# DIO-BNC_Supply.net
KiCad netlist of a schematic drawn in Altium Designer
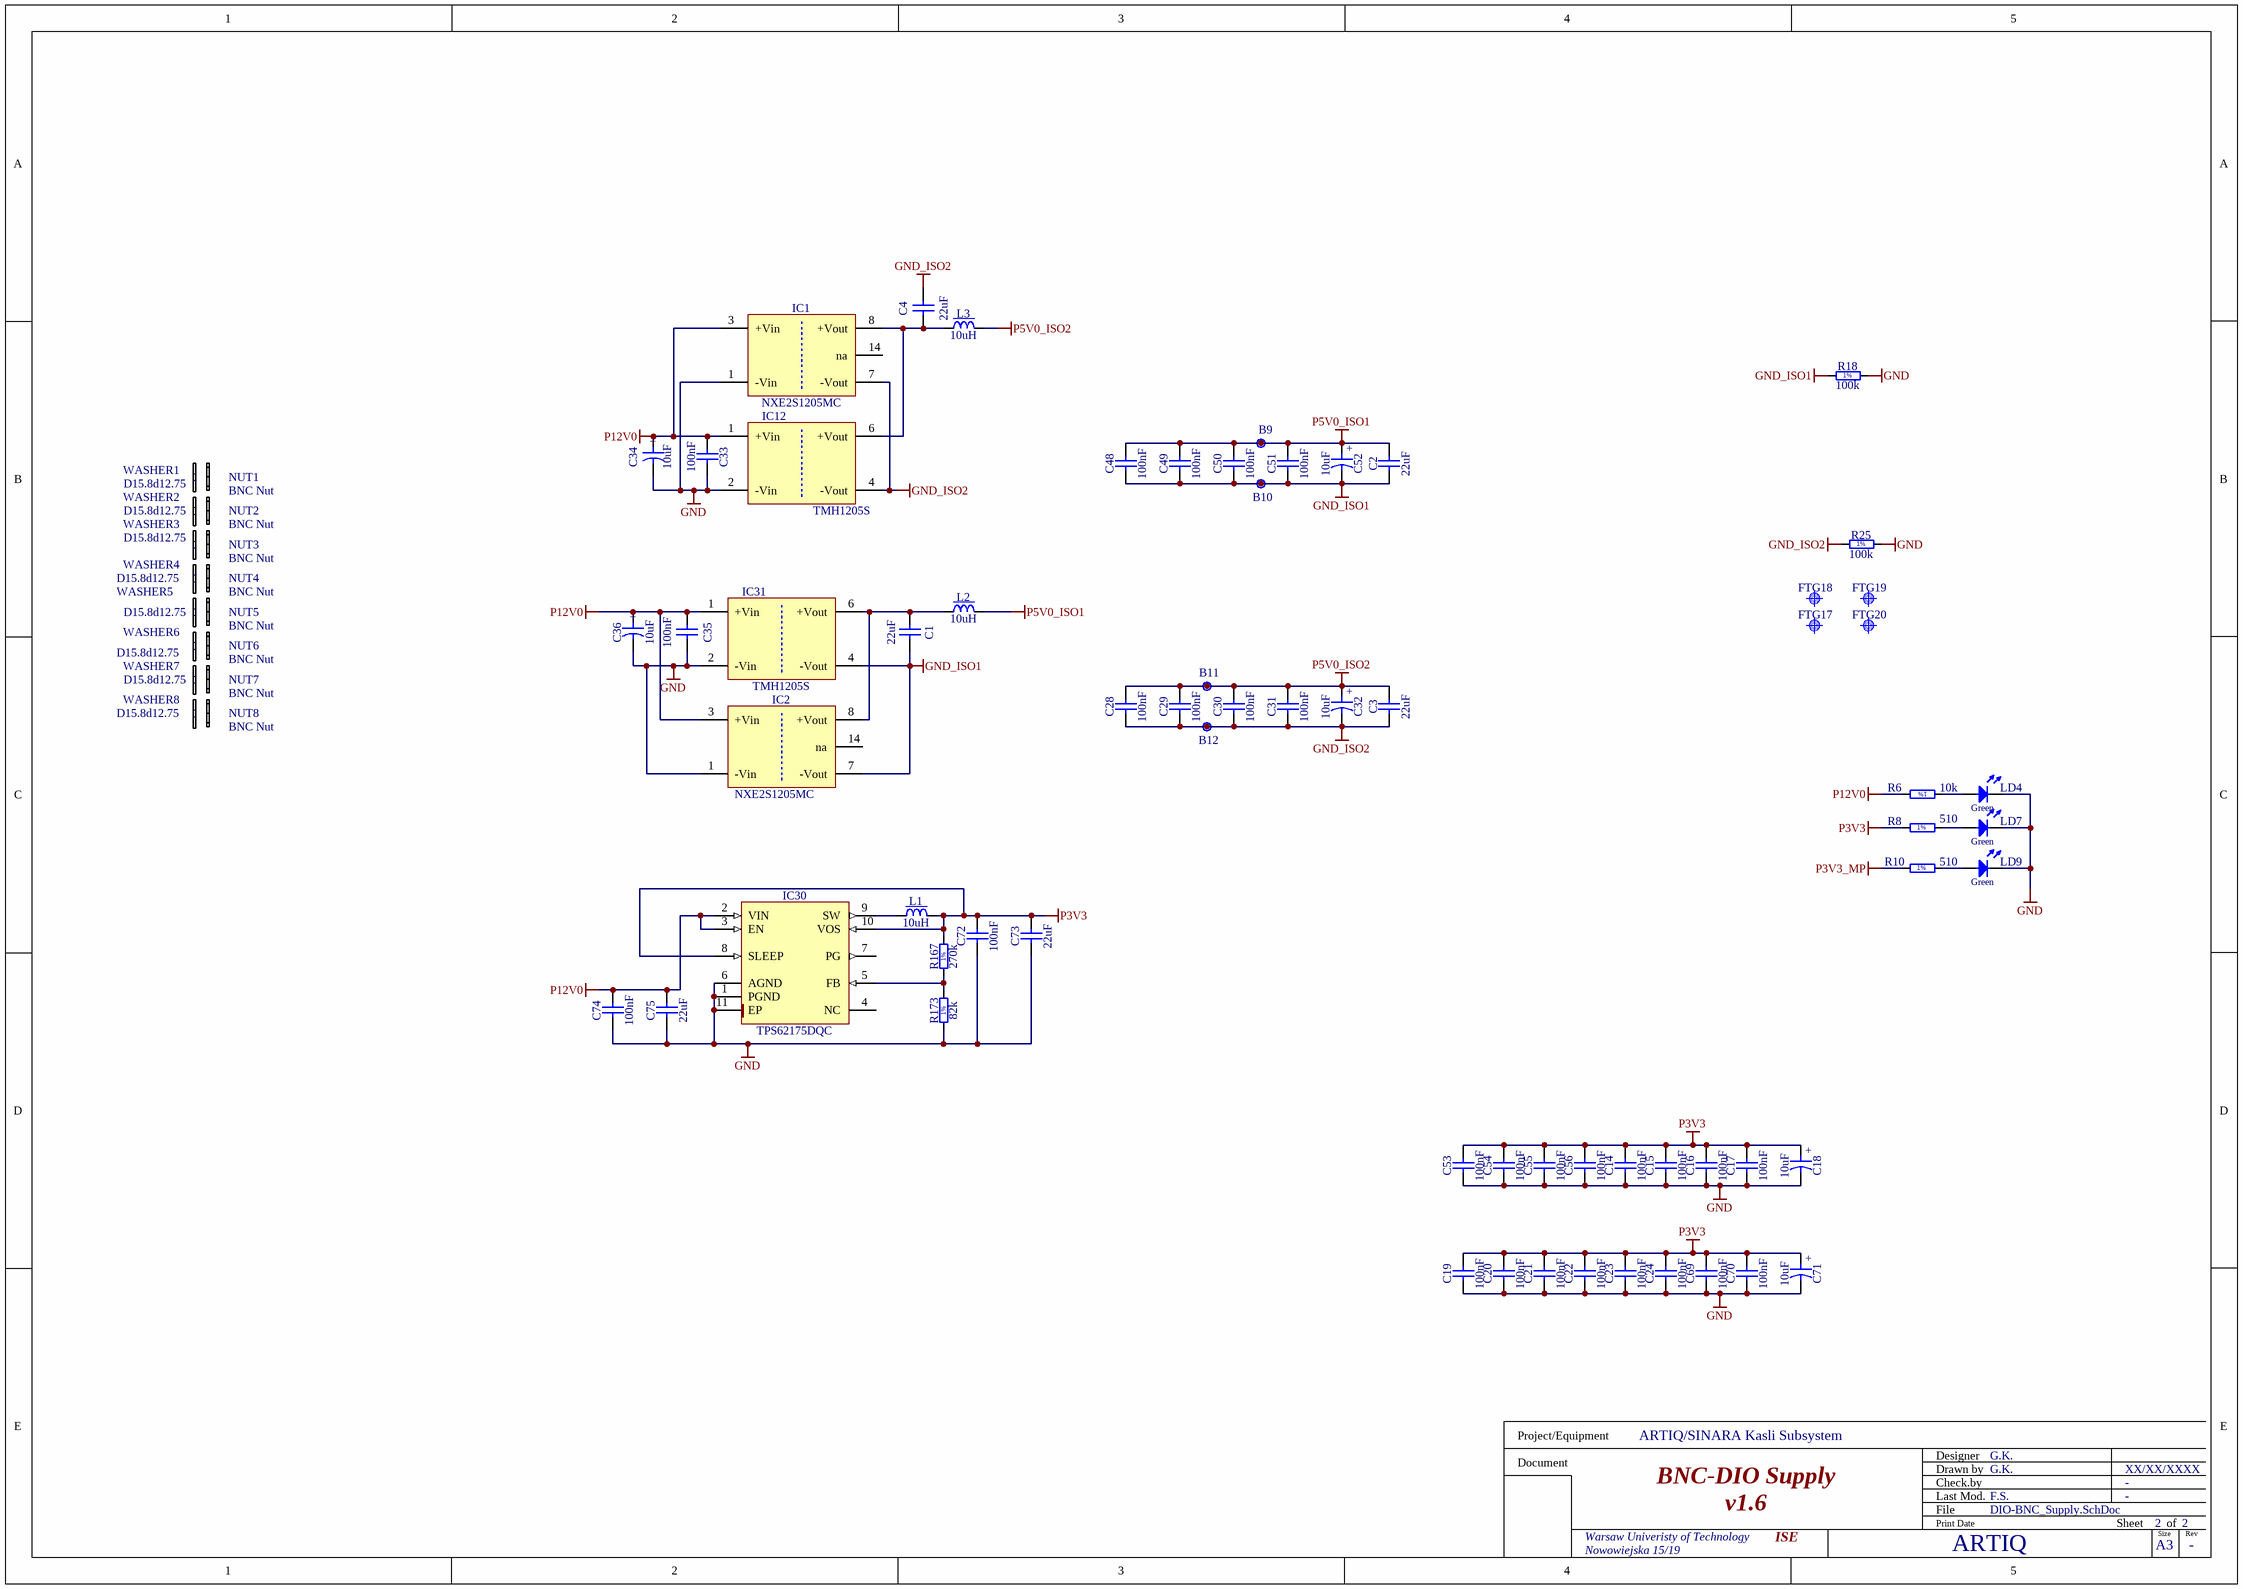
[diagram p0: DIO-BNC_Supply.SchDoc]

(export (version "E")
  (design (tool "Eeschema 10.0.6"))
  (components
    (comp (ref "B9")
      (value "Plated Hole")
      (footprint "c130h60")
      (description "Single Terminal Socket")
      (fields (field (name "PART NUMBER") "PLATED_HOLE0.6_PAD1.3") (field (name "AUTHOR") "CERN DEM MR"))
      (libsource (lib "Eletro-mechanical") (part "Single Terminal Socket"))
    )
    (comp (ref "B10")
      (value "Plated Hole")
      (footprint "c130h60")
      (description "Single Terminal Socket")
      (fields (field (name "PART NUMBER") "PLATED_HOLE0.6_PAD1.3") (field (name "AUTHOR") "CERN DEM MR"))
      (libsource (lib "Eletro-mechanical") (part "Single Terminal Socket"))
    )
    (comp (ref "B11")
      (value "Plated Hole")
      (footprint "c130h60")
      (description "Single Terminal Socket")
      (fields (field (name "PART NUMBER") "PLATED_HOLE0.6_PAD1.3") (field (name "AUTHOR") "CERN DEM MR"))
      (libsource (lib "Eletro-mechanical") (part "Single Terminal Socket"))
    )
    (comp (ref "B12")
      (value "Plated Hole")
      (footprint "c130h60")
      (description "Single Terminal Socket")
      (fields (field (name "PART NUMBER") "PLATED_HOLE0.6_PAD1.3") (field (name "AUTHOR") "CERN DEM MR"))
      (libsource (lib "Eletro-mechanical") (part "Single Terminal Socket"))
    )
    (comp (ref "C1")
      (value "22uF")
      (footprint "CAPC2012X135N")
      (description "Non-polarised capacitor")
      (fields
        (field (name "PART NUMBER") "CC0805_22UF_16V_10%_X5R")
        (field (name "VOLTAGE") "16V")
        (field (name "AUTHOR") "CERN DEM JLC")
      )
      (libsource (lib "Capacitors") (part "Capacitor - non polarized"))
    )
    (comp (ref "C2")
      (value "22uF")
      (footprint "CAPC2012X135N")
      (description "Non-polarised capacitor")
      (fields
        (field (name "PART NUMBER") "CC0805_22UF_16V_10%_X5R")
        (field (name "VOLTAGE") "16V")
        (field (name "AUTHOR") "CERN DEM JLC")
      )
      (libsource (lib "Capacitors") (part "Capacitor - non polarized"))
    )
    (comp (ref "C3")
      (value "22uF")
      (footprint "CAPC2012X135N")
      (description "Non-polarised capacitor")
      (fields
        (field (name "PART NUMBER") "CC0805_22UF_16V_10%_X5R")
        (field (name "VOLTAGE") "16V")
        (field (name "AUTHOR") "CERN DEM JLC")
      )
      (libsource (lib "Capacitors") (part "Capacitor - non polarized"))
    )
    (comp (ref "C4")
      (value "22uF")
      (footprint "CAPC2012X135N")
      (description "Non-polarised capacitor")
      (fields
        (field (name "PART NUMBER") "CC0805_22UF_16V_10%_X5R")
        (field (name "VOLTAGE") "16V")
        (field (name "AUTHOR") "CERN DEM JLC")
      )
      (libsource (lib "Capacitors") (part "Capacitor - non polarized"))
    )
    (comp (ref "C14")
      (value "100nF")
      (footprint "CAPC1005X55N")
      (description "Non-polarised capacitor")
      (fields
        (field (name "PART NUMBER") "CC0402_100NF_16V_10%_X5R")
        (field (name "VOLTAGE") "16V")
        (field (name "AUTHOR") "CERN DEM JLC")
      )
      (libsource (lib "Capacitors") (part "Capacitor - non polarized"))
    )
    (comp (ref "C15")
      (value "100nF")
      (footprint "CAPC1005X55N")
      (description "Non-polarised capacitor")
      (fields
        (field (name "PART NUMBER") "CC0402_100NF_16V_10%_X5R")
        (field (name "VOLTAGE") "16V")
        (field (name "AUTHOR") "CERN DEM JLC")
      )
      (libsource (lib "Capacitors") (part "Capacitor - non polarized"))
    )
    (comp (ref "C16")
      (value "100nF")
      (footprint "CAPC1005X55N")
      (description "Non-polarised capacitor")
      (fields
        (field (name "PART NUMBER") "CC0402_100NF_16V_10%_X5R")
        (field (name "VOLTAGE") "16V")
        (field (name "AUTHOR") "CERN DEM JLC")
      )
      (libsource (lib "Capacitors") (part "Capacitor - non polarized"))
    )
    (comp (ref "C17")
      (value "100nF")
      (footprint "CAPC1005X55N")
      (description "Non-polarised capacitor")
      (fields
        (field (name "PART NUMBER") "CC0402_100NF_16V_10%_X5R")
        (field (name "VOLTAGE") "16V")
        (field (name "AUTHOR") "CERN DEM JLC")
      )
      (libsource (lib "Capacitors") (part "Capacitor - non polarized"))
    )
    (comp (ref "C18")
      (value "10uF")
      (footprint "CAPAE430X540N")
      (description "Polarised capacitor")
      (fields
        (field (name "PART NUMBER") "CAE430-540_10UF_16V_20%")
        (field (name "VOLTAGE") "16V")
        (field (name "AUTHOR") "CERN DEM JLC")
      )
      (libsource (lib "Capacitors") (part "Capacitor - polarized"))
    )
    (comp (ref "C19")
      (value "100nF")
      (footprint "CAPC1005X55N")
      (description "Non-polarised capacitor")
      (fields
        (field (name "PART NUMBER") "CC0402_100NF_16V_10%_X5R")
        (field (name "VOLTAGE") "16V")
        (field (name "AUTHOR") "CERN DEM JLC")
      )
      (libsource (lib "Capacitors") (part "Capacitor - non polarized"))
    )
    (comp (ref "C20")
      (value "100nF")
      (footprint "CAPC1005X55N")
      (description "Non-polarised capacitor")
      (fields
        (field (name "PART NUMBER") "CC0402_100NF_16V_10%_X5R")
        (field (name "VOLTAGE") "16V")
        (field (name "AUTHOR") "CERN DEM JLC")
      )
      (libsource (lib "Capacitors") (part "Capacitor - non polarized"))
    )
    (comp (ref "C21")
      (value "100nF")
      (footprint "CAPC1005X55N")
      (description "Non-polarised capacitor")
      (fields
        (field (name "PART NUMBER") "CC0402_100NF_16V_10%_X5R")
        (field (name "VOLTAGE") "16V")
        (field (name "AUTHOR") "CERN DEM JLC")
      )
      (libsource (lib "Capacitors") (part "Capacitor - non polarized"))
    )
    (comp (ref "C22")
      (value "100nF")
      (footprint "CAPC1005X55N")
      (description "Non-polarised capacitor")
      (fields
        (field (name "PART NUMBER") "CC0402_100NF_16V_10%_X5R")
        (field (name "VOLTAGE") "16V")
        (field (name "AUTHOR") "CERN DEM JLC")
      )
      (libsource (lib "Capacitors") (part "Capacitor - non polarized"))
    )
    (comp (ref "C23")
      (value "100nF")
      (footprint "CAPC1005X55N")
      (description "Non-polarised capacitor")
      (fields
        (field (name "PART NUMBER") "CC0402_100NF_16V_10%_X5R")
        (field (name "VOLTAGE") "16V")
        (field (name "AUTHOR") "CERN DEM JLC")
      )
      (libsource (lib "Capacitors") (part "Capacitor - non polarized"))
    )
    (comp (ref "C24")
      (value "100nF")
      (footprint "CAPC1005X55N")
      (description "Non-polarised capacitor")
      (fields
        (field (name "PART NUMBER") "CC0402_100NF_16V_10%_X5R")
        (field (name "VOLTAGE") "16V")
        (field (name "AUTHOR") "CERN DEM JLC")
      )
      (libsource (lib "Capacitors") (part "Capacitor - non polarized"))
    )
    (comp (ref "C28")
      (value "100nF")
      (footprint "CAPC1005X55N")
      (description "Non-polarised capacitor")
      (fields
        (field (name "PART NUMBER") "CC0402_100NF_16V_10%_X5R")
        (field (name "VOLTAGE") "16V")
        (field (name "AUTHOR") "CERN DEM JLC")
      )
      (libsource (lib "Capacitors") (part "Capacitor - non polarized"))
    )
    (comp (ref "C29")
      (value "100nF")
      (footprint "CAPC1005X55N")
      (description "Non-polarised capacitor")
      (fields
        (field (name "PART NUMBER") "CC0402_100NF_16V_10%_X5R")
        (field (name "VOLTAGE") "16V")
        (field (name "AUTHOR") "CERN DEM JLC")
      )
      (libsource (lib "Capacitors") (part "Capacitor - non polarized"))
    )
    (comp (ref "C30")
      (value "100nF")
      (footprint "CAPC1005X55N")
      (description "Non-polarised capacitor")
      (fields
        (field (name "PART NUMBER") "CC0402_100NF_16V_10%_X5R")
        (field (name "VOLTAGE") "16V")
        (field (name "AUTHOR") "CERN DEM JLC")
      )
      (libsource (lib "Capacitors") (part "Capacitor - non polarized"))
    )
    (comp (ref "C31")
      (value "100nF")
      (footprint "CAPC1005X55N")
      (description "Non-polarised capacitor")
      (fields
        (field (name "PART NUMBER") "CC0402_100NF_16V_10%_X5R")
        (field (name "VOLTAGE") "16V")
        (field (name "AUTHOR") "CERN DEM JLC")
      )
      (libsource (lib "Capacitors") (part "Capacitor - non polarized"))
    )
    (comp (ref "C32")
      (value "10uF")
      (footprint "CAPAE430X540N")
      (description "Polarised capacitor")
      (fields
        (field (name "PART NUMBER") "CAE430-540_10UF_16V_20%")
        (field (name "VOLTAGE") "16V")
        (field (name "AUTHOR") "CERN DEM JLC")
      )
      (libsource (lib "Capacitors") (part "Capacitor - polarized"))
    )
    (comp (ref "C33")
      (value "100nF")
      (footprint "CAPC1005X55N")
      (description "Non-polarised capacitor")
      (fields
        (field (name "PART NUMBER") "CC0402_100NF_16V_10%_X5R")
        (field (name "VOLTAGE") "16V")
        (field (name "AUTHOR") "CERN DEM JLC")
      )
      (libsource (lib "Capacitors") (part "Capacitor - non polarized"))
    )
    (comp (ref "C34")
      (value "10uF")
      (footprint "CAPAE430X540N")
      (description "Polarised capacitor")
      (fields
        (field (name "PART NUMBER") "CAE430-540_10UF_16V_20%")
        (field (name "VOLTAGE") "16V")
        (field (name "AUTHOR") "CERN DEM JLC")
      )
      (libsource (lib "") (part "Capacitor - polarized_1"))
    )
    (comp (ref "C35")
      (value "100nF")
      (footprint "CAPC1005X55N")
      (description "Non-polarised capacitor")
      (fields
        (field (name "PART NUMBER") "CC0402_100NF_16V_10%_X5R")
        (field (name "VOLTAGE") "16V")
        (field (name "AUTHOR") "CERN DEM JLC")
      )
      (libsource (lib "Capacitors") (part "Capacitor - non polarized"))
    )
    (comp (ref "C36")
      (value "10uF")
      (footprint "CAPAE430X540N")
      (description "Polarised capacitor")
      (fields
        (field (name "PART NUMBER") "CAE430-540_10UF_16V_20%")
        (field (name "VOLTAGE") "16V")
        (field (name "AUTHOR") "CERN DEM JLC")
      )
      (libsource (lib "") (part "Capacitor - polarized_1"))
    )
    (comp (ref "C48")
      (value "100nF")
      (footprint "CAPC1005X55N")
      (description "Non-polarised capacitor")
      (fields
        (field (name "PART NUMBER") "CC0402_100NF_16V_10%_X5R")
        (field (name "VOLTAGE") "16V")
        (field (name "AUTHOR") "CERN DEM JLC")
      )
      (libsource (lib "Capacitors") (part "Capacitor - non polarized"))
    )
    (comp (ref "C49")
      (value "100nF")
      (footprint "CAPC1005X55N")
      (description "Non-polarised capacitor")
      (fields
        (field (name "PART NUMBER") "CC0402_100NF_16V_10%_X5R")
        (field (name "VOLTAGE") "16V")
        (field (name "AUTHOR") "CERN DEM JLC")
      )
      (libsource (lib "Capacitors") (part "Capacitor - non polarized"))
    )
    (comp (ref "C50")
      (value "100nF")
      (footprint "CAPC1005X55N")
      (description "Non-polarised capacitor")
      (fields
        (field (name "PART NUMBER") "CC0402_100NF_16V_10%_X5R")
        (field (name "VOLTAGE") "16V")
        (field (name "AUTHOR") "CERN DEM JLC")
      )
      (libsource (lib "Capacitors") (part "Capacitor - non polarized"))
    )
    (comp (ref "C51")
      (value "100nF")
      (footprint "CAPC1005X55N")
      (description "Non-polarised capacitor")
      (fields
        (field (name "PART NUMBER") "CC0402_100NF_16V_10%_X5R")
        (field (name "VOLTAGE") "16V")
        (field (name "AUTHOR") "CERN DEM JLC")
      )
      (libsource (lib "Capacitors") (part "Capacitor - non polarized"))
    )
    (comp (ref "C52")
      (value "10uF")
      (footprint "CAPAE430X540N")
      (description "Polarised capacitor")
      (fields
        (field (name "PART NUMBER") "CAE430-540_10UF_16V_20%")
        (field (name "VOLTAGE") "16V")
        (field (name "AUTHOR") "CERN DEM JLC")
      )
      (libsource (lib "Capacitors") (part "Capacitor - polarized"))
    )
    (comp (ref "C53")
      (value "100nF")
      (footprint "CAPC1005X55N")
      (description "Non-polarised capacitor")
      (fields
        (field (name "PART NUMBER") "CC0402_100NF_16V_10%_X5R")
        (field (name "VOLTAGE") "16V")
        (field (name "AUTHOR") "CERN DEM JLC")
      )
      (libsource (lib "Capacitors") (part "Capacitor - non polarized"))
    )
    (comp (ref "C54")
      (value "100nF")
      (footprint "CAPC1005X55N")
      (description "Non-polarised capacitor")
      (fields
        (field (name "PART NUMBER") "CC0402_100NF_16V_10%_X5R")
        (field (name "VOLTAGE") "16V")
        (field (name "AUTHOR") "CERN DEM JLC")
      )
      (libsource (lib "Capacitors") (part "Capacitor - non polarized"))
    )
    (comp (ref "C55")
      (value "100nF")
      (footprint "CAPC1005X55N")
      (description "Non-polarised capacitor")
      (fields
        (field (name "PART NUMBER") "CC0402_100NF_16V_10%_X5R")
        (field (name "VOLTAGE") "16V")
        (field (name "AUTHOR") "CERN DEM JLC")
      )
      (libsource (lib "Capacitors") (part "Capacitor - non polarized"))
    )
    (comp (ref "C56")
      (value "100nF")
      (footprint "CAPC1005X55N")
      (description "Non-polarised capacitor")
      (fields
        (field (name "PART NUMBER") "CC0402_100NF_16V_10%_X5R")
        (field (name "VOLTAGE") "16V")
        (field (name "AUTHOR") "CERN DEM JLC")
      )
      (libsource (lib "Capacitors") (part "Capacitor - non polarized"))
    )
    (comp (ref "C69")
      (value "100nF")
      (footprint "CAPC1005X55N")
      (description "Non-polarised capacitor")
      (fields
        (field (name "PART NUMBER") "CC0402_100NF_16V_10%_X5R")
        (field (name "VOLTAGE") "16V")
        (field (name "AUTHOR") "CERN DEM JLC")
      )
      (libsource (lib "Capacitors") (part "Capacitor - non polarized"))
    )
    (comp (ref "C70")
      (value "100nF")
      (footprint "CAPC1005X55N")
      (description "Non-polarised capacitor")
      (fields
        (field (name "PART NUMBER") "CC0402_100NF_16V_10%_X5R")
        (field (name "VOLTAGE") "16V")
        (field (name "AUTHOR") "CERN DEM JLC")
      )
      (libsource (lib "Capacitors") (part "Capacitor - non polarized"))
    )
    (comp (ref "C71")
      (value "10uF")
      (footprint "CAPAE430X540N")
      (description "Polarised capacitor")
      (fields
        (field (name "PART NUMBER") "CAE430-540_10UF_16V_20%")
        (field (name "VOLTAGE") "16V")
        (field (name "AUTHOR") "CERN DEM JLC")
      )
      (libsource (lib "Capacitors") (part "Capacitor - polarized"))
    )
    (comp (ref "C72")
      (value "100nF")
      (footprint "CAPC1005X55N")
      (description "Non-polarised capacitor")
      (fields
        (field (name "PART NUMBER") "CC0402_100NF_16V_10%_X5R")
        (field (name "VOLTAGE") "16V")
        (field (name "AUTHOR") "CERN DEM JLC")
      )
      (libsource (lib "Capacitors") (part "Capacitor - non polarized"))
    )
    (comp (ref "C73")
      (value "22uF")
      (footprint "CAPC2012X135N")
      (description "Non-polarised capacitor")
      (fields
        (field (name "PART NUMBER") "CC0805_22UF_16V_10%_X5R")
        (field (name "VOLTAGE") "16V")
        (field (name "AUTHOR") "CERN DEM JLC")
      )
      (libsource (lib "Capacitors") (part "Capacitor - non polarized"))
    )
    (comp (ref "C74")
      (value "100nF")
      (footprint "CAPC1005X55N")
      (description "Non-polarised capacitor")
      (fields
        (field (name "PART NUMBER") "CC0402_100NF_16V_10%_X5R")
        (field (name "VOLTAGE") "16V")
        (field (name "AUTHOR") "CERN DEM JLC")
      )
      (libsource (lib "Capacitors") (part "Capacitor - non polarized"))
    )
    (comp (ref "C75")
      (value "22uF")
      (footprint "CAPC2012X135N")
      (description "Non-polarised capacitor")
      (fields
        (field (name "PART NUMBER") "CC0805_22UF_16V_10%_X5R")
        (field (name "VOLTAGE") "16V")
        (field (name "AUTHOR") "CERN DEM JLC")
      )
      (libsource (lib "Capacitors") (part "Capacitor - non polarized"))
    )
    (comp (ref "FTG17")
      (value "Use only in PCB")
      (footprint "FIDUCIAL_TOP_C100-200")
      (description "Fiducial Target")
      (fields (field (name "PART NUMBER") "FIDUCIAL_TARGET_C100-200") (field (name "AUTHOR") "CERN DEM JLC"))
      (libsource (lib "Eletro-mechanical") (part "Fiducial Target"))
    )
    (comp (ref "FTG18")
      (value "Use only in PCB")
      (footprint "FIDUCIAL_TOP_S100-200")
      (description "Fiducial Target")
      (fields (field (name "PART NUMBER") "FIDUCIAL_TARGET_S100-200") (field (name "AUTHOR") "CERN DEM JLC"))
      (libsource (lib "Eletro-mechanical") (part "Fiducial Target"))
    )
    (comp (ref "FTG19")
      (value "Use only in PCB")
      (footprint "FIDUCIAL_TOP_S200-400")
      (description "Fiducial Target")
      (fields (field (name "PART NUMBER") "FIDUCIAL_TARGET_S200-400") (field (name "AUTHOR") "CERN DEM JLC"))
      (libsource (lib "Eletro-mechanical") (part "Fiducial Target"))
    )
    (comp (ref "FTG20")
      (value "Use only in PCB")
      (footprint "FIDUCIAL_TOP_S100-200")
      (description "Fiducial Target")
      (fields (field (name "PART NUMBER") "FIDUCIAL_TARGET_S100-200") (field (name "AUTHOR") "CERN DEM JLC"))
      (libsource (lib "Eletro-mechanical") (part "Fiducial Target"))
    )
    (comp (ref "IC1")
      (value "NXE2S1205MC")
      (footprint "DCDC_MURATA_NXE2")
      (description "MURATA, NXE2 Serie, Dual Output DCDC Converter")
      (fields (field (name "MANUFACTURER") "MURATA POWER SOLUTIONS") (field (name "AUTHOR") "CERN DEM MR"))
      (libsource (lib "LIBRARY_SCH") (part "DCDC_MURATA_NXE2S1205MC"))
    )
    (comp (ref "IC2")
      (value "NXE2S1205MC")
      (footprint "DCDC_MURATA_NXE2")
      (description "MURATA, NXE2 Serie, Dual Output DCDC Converter")
      (fields (field (name "MANUFACTURER") "MURATA POWER SOLUTIONS") (field (name "AUTHOR") "CERN DEM MR"))
      (libsource (lib "LIBRARY_SCH") (part "DCDC_MURATA_NXE2S1205MC"))
    )
    (comp (ref "IC12")
      (value "TMH1205S")
      (footprint "DCDC_TRACO_TMA")
      (description "12V ±10% to 5V, Iout (max) 400mA, 2W DC-DC Converter")
      (fields (field (name "MANUFACTURER") "TRACO POWER") (field (name "AUTHOR") "GK"))
      (libsource (lib "Regulators_SMPS") (part "DC/DC_TRACO_TMH1205S"))
    )
    (comp (ref "IC30")
      (value "TPS62175DQC")
      (footprint "SON50P200X300X80-11N-R94X250")
      (description "4.75-28VDC to 1-6VDC, 500mA Step-Down Converter With Sleep Mode")
      (fields (field (name "MANUFACTURER") "TEXAS INSTRUMENTS") (field (name "AUTHOR") "CERN DEM JMW"))
      (libsource (lib "ICs And Semiconductors") (part "TPS62175"))
    )
    (comp (ref "IC31")
      (value "TMH1205S")
      (footprint "DCDC_TRACO_TMA")
      (description "12V ±10% to 5V, Iout (max) 400mA, 2W DC-DC Converter")
      (fields (field (name "MANUFACTURER") "TRACO POWER") (field (name "AUTHOR") "GK"))
      (libsource (lib "Regulators_SMPS") (part "DC/DC_TRACO_TMH1205S"))
    )
    (comp (ref "L1")
      (value "10uH")
      (footprint "IND_MURATA-PS_8400")
      (description "Inductor With Core")
      (fields
        (field (name "PART NUMBER") "IND_10UH_10%_MURATA-PS_8400")
        (field (name "POWER") "950mA")
        (field (name "AUTHOR") "CERN DEM JLC")
      )
      (libsource (lib "") (part "Inductor With Magnetic core_1"))
    )
    (comp (ref "L2")
      (value "10uH")
      (footprint "IND_MURATA-PS_8400")
      (description "Inductor With Core")
      (fields
        (field (name "PART NUMBER") "IND_10UH_10%_MURATA-PS_8400")
        (field (name "POWER") "950mA")
        (field (name "AUTHOR") "CERN DEM JLC")
      )
      (libsource (lib "Inductors & Transformers") (part "Inductor With Magnetic core"))
    )
    (comp (ref "L3")
      (value "10uH")
      (footprint "IND_MURATA-PS_8400")
      (description "Inductor With Core")
      (fields
        (field (name "PART NUMBER") "IND_10UH_10%_MURATA-PS_8400")
        (field (name "POWER") "950mA")
        (field (name "AUTHOR") "CERN DEM JLC")
      )
      (libsource (lib "Inductors & Transformers") (part "Inductor With Magnetic core"))
    )
    (comp (ref "LD4")
      (value "Green")
      (footprint "LED_KINGBRIGHT_KPH-1608CGCK")
      (description "LED Green 1C 2A")
      (fields
        (field (name "PART NUMBER") "LED_KINGBRIGHT_KPH-1608CGCK")
        (field (name "MANUFACTURER") "KINGBRIGHT")
        (field (name "AUTHOR") "CERN DEM JLC")
      )
      (libsource (lib "ICs And Semiconductors") (part "LED Green 1C 2A"))
    )
    (comp (ref "LD7")
      (value "Green")
      (footprint "LED_KINGBRIGHT_KPH-1608CGCK")
      (description "LED Green 1C 2A")
      (fields
        (field (name "PART NUMBER") "LED_KINGBRIGHT_KPH-1608CGCK")
        (field (name "MANUFACTURER") "KINGBRIGHT")
        (field (name "AUTHOR") "CERN DEM JLC")
      )
      (libsource (lib "ICs And Semiconductors") (part "LED Green 1C 2A"))
    )
    (comp (ref "LD9")
      (value "Green")
      (footprint "LED_KINGBRIGHT_KPH-1608CGCK")
      (description "LED Green 1C 2A")
      (fields
        (field (name "PART NUMBER") "LED_KINGBRIGHT_KPH-1608CGCK")
        (field (name "MANUFACTURER") "KINGBRIGHT")
        (field (name "AUTHOR") "CERN DEM JLC")
      )
      (libsource (lib "ICs And Semiconductors") (part "LED Green 1C 2A"))
    )
    (comp (ref "NUT1")
      (value "BNC Nut")
      (footprint "TE_1-329631-2")
      (description "BNC nut")
      (fields
        (field (name "PART NUMBER") "TE_1-329631-2")
        (field (name "MANUFACTURER") "TE")
        (field (name "AUTHOR") "CERN DEM JLC")
      )
      (libsource (lib "LIBRARY_SCH") (part "MECH_BNC_NUT"))
    )
    (comp (ref "NUT2")
      (value "BNC Nut")
      (footprint "TE_1-329631-2")
      (description "BNC nut")
      (fields
        (field (name "PART NUMBER") "TE_1-329631-2")
        (field (name "MANUFACTURER") "TE")
        (field (name "AUTHOR") "CERN DEM JLC")
      )
      (libsource (lib "LIBRARY_SCH") (part "MECH_BNC_NUT"))
    )
    (comp (ref "NUT3")
      (value "BNC Nut")
      (footprint "TE_1-329631-2")
      (description "BNC nut")
      (fields
        (field (name "PART NUMBER") "TE_1-329631-2")
        (field (name "MANUFACTURER") "TE")
        (field (name "AUTHOR") "CERN DEM JLC")
      )
      (libsource (lib "LIBRARY_SCH") (part "MECH_BNC_NUT"))
    )
    (comp (ref "NUT4")
      (value "BNC Nut")
      (footprint "TE_1-329631-2")
      (description "BNC nut")
      (fields
        (field (name "PART NUMBER") "TE_1-329631-2")
        (field (name "MANUFACTURER") "TE")
        (field (name "AUTHOR") "CERN DEM JLC")
      )
      (libsource (lib "LIBRARY_SCH") (part "MECH_BNC_NUT"))
    )
    (comp (ref "NUT5")
      (value "BNC Nut")
      (footprint "TE_1-329631-2")
      (description "BNC nut")
      (fields
        (field (name "PART NUMBER") "TE_1-329631-2")
        (field (name "MANUFACTURER") "TE")
        (field (name "AUTHOR") "CERN DEM JLC")
      )
      (libsource (lib "LIBRARY_SCH") (part "MECH_BNC_NUT"))
    )
    (comp (ref "NUT6")
      (value "BNC Nut")
      (footprint "TE_1-329631-2")
      (description "BNC nut")
      (fields
        (field (name "PART NUMBER") "TE_1-329631-2")
        (field (name "MANUFACTURER") "TE")
        (field (name "AUTHOR") "CERN DEM JLC")
      )
      (libsource (lib "LIBRARY_SCH") (part "MECH_BNC_NUT"))
    )
    (comp (ref "NUT7")
      (value "BNC Nut")
      (footprint "TE_1-329631-2")
      (description "BNC nut")
      (fields
        (field (name "PART NUMBER") "TE_1-329631-2")
        (field (name "MANUFACTURER") "TE")
        (field (name "AUTHOR") "CERN DEM JLC")
      )
      (libsource (lib "LIBRARY_SCH") (part "MECH_BNC_NUT"))
    )
    (comp (ref "NUT8")
      (value "BNC Nut")
      (footprint "TE_1-329631-2")
      (description "BNC nut")
      (fields
        (field (name "PART NUMBER") "TE_1-329631-2")
        (field (name "MANUFACTURER") "TE")
        (field (name "AUTHOR") "CERN DEM JLC")
      )
      (libsource (lib "LIBRARY_SCH") (part "MECH_BNC_NUT"))
    )
    (comp (ref "R6")
      (value "10k")
      (footprint "RESC1005X40N")
      (description "Resistor - 1%")
      (fields
        (field (name "PART NUMBER") "R0402_10K_1%_0.0625W_100PPM")
        (field (name "POWER") "0.0625W")
        (field (name "AUTHOR") "CERN DEM JLC")
      )
      (libsource (lib "Resistors") (part "Resistor - 1%"))
    )
    (comp (ref "R8")
      (value "510")
      (footprint "RESC1005X40N")
      (description "Resistor - 1%")
      (fields
        (field (name "PART NUMBER") "R0402_510R_1%_0.0625W_100PPM")
        (field (name "POWER") "0.0625W")
        (field (name "AUTHOR") "CERN DEM JLC")
      )
      (libsource (lib "Resistors") (part "Resistor - 1%"))
    )
    (comp (ref "R10")
      (value "510")
      (footprint "RESC1005X40N")
      (description "Resistor - 1%")
      (fields
        (field (name "PART NUMBER") "R0402_510R_1%_0.0625W_100PPM")
        (field (name "POWER") "0.0625W")
        (field (name "AUTHOR") "CERN DEM JLC")
      )
      (libsource (lib "Resistors") (part "Resistor - 1%"))
    )
    (comp (ref "R18")
      (value "100k")
      (footprint "RESC2012X60N")
      (description "Resistor - 1%")
      (fields
        (field (name "PART NUMBER") "R0805_100K_1%_0.125W_100PPM")
        (field (name "POWER") "0.125W")
        (field (name "AUTHOR") "CERN DEM JLC")
      )
      (libsource (lib "Resistors") (part "Resistor - 1%"))
    )
    (comp (ref "R25")
      (value "100k")
      (footprint "RESC2012X60N")
      (description "Resistor - 1%")
      (fields
        (field (name "PART NUMBER") "R0805_100K_1%_0.125W_100PPM")
        (field (name "POWER") "0.125W")
        (field (name "AUTHOR") "CERN DEM JLC")
      )
      (libsource (lib "Resistors") (part "Resistor - 1%"))
    )
    (comp (ref "R167")
      (value "270k")
      (footprint "RESC1608X55N")
      (description "Resistor - 1%")
      (fields
        (field (name "PART NUMBER") "R0603_270K_1%_0.1W_100PPM")
        (field (name "POWER") "0.1W")
        (field (name "AUTHOR") "CERN DEM JLC")
      )
      (libsource (lib "Resistors") (part "Resistor - 1%"))
    )
    (comp (ref "R173")
      (value "82k")
      (footprint "RESC1608X55N")
      (description "Resistor - 1%")
      (fields
        (field (name "PART NUMBER") "R0603_82K_1%_0.1W_100PPM")
        (field (name "POWER") "0.1W")
        (field (name "AUTHOR") "CERN DEM JLC")
      )
      (libsource (lib "Resistors") (part "Resistor - 1%"))
    )
    (comp (ref "WASHER1")
      (value "D15.8d12.75")
      (footprint "TE_1-1634817-0")
      (description "BNC Washer")
      (fields
        (field (name "PART NUMBER") "TE_1-1634817-0")
        (field (name "MANUFACTURER") "TE")
        (field (name "AUTHOR") "GK")
      )
      (libsource (lib "LIBRARY_SCH") (part "MECH_BNC_WASHER"))
    )
    (comp (ref "WASHER2")
      (value "D15.8d12.75")
      (footprint "TE_1-1634817-0")
      (description "BNC Washer")
      (fields
        (field (name "PART NUMBER") "TE_1-1634817-0")
        (field (name "MANUFACTURER") "TE")
        (field (name "AUTHOR") "GK")
      )
      (libsource (lib "LIBRARY_SCH") (part "MECH_BNC_WASHER"))
    )
    (comp (ref "WASHER3")
      (value "D15.8d12.75")
      (footprint "TE_1-1634817-0")
      (description "BNC Washer")
      (fields
        (field (name "PART NUMBER") "TE_1-1634817-0")
        (field (name "MANUFACTURER") "TE")
        (field (name "AUTHOR") "GK")
      )
      (libsource (lib "LIBRARY_SCH") (part "MECH_BNC_WASHER"))
    )
    (comp (ref "WASHER4")
      (value "D15.8d12.75")
      (footprint "TE_1-1634817-0")
      (description "BNC Washer")
      (fields
        (field (name "PART NUMBER") "TE_1-1634817-0")
        (field (name "MANUFACTURER") "TE")
        (field (name "AUTHOR") "GK")
      )
      (libsource (lib "LIBRARY_SCH") (part "MECH_BNC_WASHER"))
    )
    (comp (ref "WASHER5")
      (value "D15.8d12.75")
      (footprint "TE_1-1634817-0")
      (description "BNC Washer")
      (fields
        (field (name "PART NUMBER") "TE_1-1634817-0")
        (field (name "MANUFACTURER") "TE")
        (field (name "AUTHOR") "GK")
      )
      (libsource (lib "LIBRARY_SCH") (part "MECH_BNC_WASHER"))
    )
    (comp (ref "WASHER6")
      (value "D15.8d12.75")
      (footprint "TE_1-1634817-0")
      (description "BNC Washer")
      (fields
        (field (name "PART NUMBER") "TE_1-1634817-0")
        (field (name "MANUFACTURER") "TE")
        (field (name "AUTHOR") "GK")
      )
      (libsource (lib "LIBRARY_SCH") (part "MECH_BNC_WASHER"))
    )
    (comp (ref "WASHER7")
      (value "D15.8d12.75")
      (footprint "TE_1-1634817-0")
      (description "BNC Washer")
      (fields
        (field (name "PART NUMBER") "TE_1-1634817-0")
        (field (name "MANUFACTURER") "TE")
        (field (name "AUTHOR") "GK")
      )
      (libsource (lib "LIBRARY_SCH") (part "MECH_BNC_WASHER"))
    )
    (comp (ref "WASHER8")
      (value "D15.8d12.75")
      (footprint "TE_1-1634817-0")
      (description "BNC Washer")
      (fields
        (field (name "PART NUMBER") "TE_1-1634817-0")
        (field (name "MANUFACTURER") "TE")
        (field (name "AUTHOR") "GK")
      )
      (libsource (lib "LIBRARY_SCH") (part "MECH_BNC_WASHER"))
    )
  )
  (nets
    (net (code "1") (name "GND") (class "Default")
      (node (ref "C14") (pin "1") (pinfunction "1_1") (pintype "passive"))
      (node (ref "C15") (pin "1") (pinfunction "1_1") (pintype "passive"))
      (node (ref "C16") (pin "1") (pinfunction "1_1") (pintype "passive"))
      (node (ref "C17") (pin "1") (pinfunction "1_1") (pintype "passive"))
      (node (ref "C18") (pin "2") (pinfunction "2_2") (pintype "passive"))
      (node (ref "C19") (pin "1") (pinfunction "1_1") (pintype "passive"))
      (node (ref "C20") (pin "1") (pinfunction "1_1") (pintype "passive"))
      (node (ref "C21") (pin "1") (pinfunction "1_1") (pintype "passive"))
      (node (ref "C22") (pin "1") (pinfunction "1_1") (pintype "passive"))
      (node (ref "C23") (pin "1") (pinfunction "1_1") (pintype "passive"))
      (node (ref "C24") (pin "1") (pinfunction "1_1") (pintype "passive"))
      (node (ref "C33") (pin "1") (pinfunction "1_1") (pintype "passive"))
      (node (ref "C34") (pin "2") (pinfunction "2_2") (pintype "passive"))
      (node (ref "C35") (pin "1") (pinfunction "1_1") (pintype "passive"))
      (node (ref "C36") (pin "2") (pinfunction "2_2") (pintype "passive"))
      (node (ref "C53") (pin "1") (pinfunction "1_1") (pintype "passive"))
      (node (ref "C54") (pin "1") (pinfunction "1_1") (pintype "passive"))
      (node (ref "C55") (pin "1") (pinfunction "1_1") (pintype "passive"))
      (node (ref "C56") (pin "1") (pinfunction "1_1") (pintype "passive"))
      (node (ref "C69") (pin "1") (pinfunction "1_1") (pintype "passive"))
      (node (ref "C70") (pin "1") (pinfunction "1_1") (pintype "passive"))
      (node (ref "C71") (pin "2") (pinfunction "2_2") (pintype "passive"))
      (node (ref "C72") (pin "1") (pinfunction "1_1") (pintype "passive"))
      (node (ref "C73") (pin "1") (pinfunction "1_1") (pintype "passive"))
      (node (ref "C74") (pin "1") (pinfunction "1_1") (pintype "passive"))
      (node (ref "C75") (pin "1") (pinfunction "1_1") (pintype "passive"))
      (node (ref "IC1") (pin "1") (pinfunction "-Vin_1") (pintype "power_in"))
      (node (ref "IC12") (pin "2") (pinfunction "-Vin_2") (pintype "power_in"))
      (node (ref "IC2") (pin "1") (pinfunction "-Vin_1") (pintype "power_in"))
      (node (ref "IC30") (pin "1") (pinfunction "PGND_1") (pintype "power_in"))
      (node (ref "IC30") (pin "11") (pinfunction "EP_11") (pintype "power_in"))
      (node (ref "IC30") (pin "6") (pinfunction "AGND_6") (pintype "power_in"))
      (node (ref "IC31") (pin "2") (pinfunction "-Vin_2") (pintype "power_in"))
      (node (ref "LD4") (pin "1") (pinfunction "C_1") (pintype "passive"))
      (node (ref "LD7") (pin "1") (pinfunction "C_1") (pintype "passive"))
      (node (ref "LD9") (pin "1") (pinfunction "C_1") (pintype "passive"))
      (node (ref "R173") (pin "1") (pinfunction "1_1") (pintype "passive"))
      (node (ref "R18") (pin "2") (pinfunction "2_2") (pintype "passive"))
      (node (ref "R25") (pin "2") (pinfunction "2_2") (pintype "passive"))
    )
    (net (code "2") (name "GND_ISO1") (class "Default")
      (node (ref "B10") (pin "1") (pinfunction "1_1") (pintype "bidirectional"))
      (node (ref "C1") (pin "1") (pinfunction "1_1") (pintype "passive"))
      (node (ref "C2") (pin "1") (pinfunction "1_1") (pintype "passive"))
      (node (ref "C48") (pin "1") (pinfunction "1_1") (pintype "passive"))
      (node (ref "C49") (pin "1") (pinfunction "1_1") (pintype "passive"))
      (node (ref "C50") (pin "1") (pinfunction "1_1") (pintype "passive"))
      (node (ref "C51") (pin "1") (pinfunction "1_1") (pintype "passive"))
      (node (ref "C52") (pin "2") (pinfunction "2_2") (pintype "passive"))
      (node (ref "IC2") (pin "7") (pinfunction "-Vout_7") (pintype "power_in"))
      (node (ref "IC31") (pin "4") (pinfunction "-Vout_4") (pintype "power_in"))
      (node (ref "R18") (pin "1") (pinfunction "1_1") (pintype "passive"))
    )
    (net (code "3") (name "GND_ISO2") (class "Default")
      (node (ref "B12") (pin "1") (pinfunction "1_1") (pintype "bidirectional"))
      (node (ref "C28") (pin "1") (pinfunction "1_1") (pintype "passive"))
      (node (ref "C29") (pin "1") (pinfunction "1_1") (pintype "passive"))
      (node (ref "C3") (pin "1") (pinfunction "1_1") (pintype "passive"))
      (node (ref "C30") (pin "1") (pinfunction "1_1") (pintype "passive"))
      (node (ref "C31") (pin "1") (pinfunction "1_1") (pintype "passive"))
      (node (ref "C32") (pin "2") (pinfunction "2_2") (pintype "passive"))
      (node (ref "C4") (pin "1") (pinfunction "1_1") (pintype "passive"))
      (node (ref "IC1") (pin "7") (pinfunction "-Vout_7") (pintype "power_in"))
      (node (ref "IC12") (pin "4") (pinfunction "-Vout_4") (pintype "power_in"))
      (node (ref "R25") (pin "1") (pinfunction "1_1") (pintype "passive"))
    )
    (net (code "4") (name "Net-(IC1-+Vout)") (class "Default")
      (node (ref "C4") (pin "2") (pinfunction "2_2") (pintype "passive"))
      (node (ref "IC1") (pin "8") (pinfunction "+Vout_8") (pintype "power_in"))
      (node (ref "IC12") (pin "6") (pinfunction "+Vout_6") (pintype "power_in"))
      (node (ref "L3") (pin "2") (pinfunction "2_2") (pintype "passive"))
    )
    (net (code "5") (name "Net-(IC2-+Vout)") (class "Default")
      (node (ref "C1") (pin "2") (pinfunction "2_2") (pintype "passive"))
      (node (ref "IC2") (pin "8") (pinfunction "+Vout_8") (pintype "power_in"))
      (node (ref "IC31") (pin "6") (pinfunction "+Vout_6") (pintype "power_in"))
      (node (ref "L2") (pin "2") (pinfunction "2_2") (pintype "passive"))
    )
    (net (code "6") (name "Net-(IC30-FB)") (class "Default")
      (node (ref "IC30") (pin "5") (pinfunction "FB_5") (pintype "input"))
      (node (ref "R167") (pin "1") (pinfunction "1_1") (pintype "passive"))
      (node (ref "R173") (pin "2") (pinfunction "2_2") (pintype "passive"))
    )
    (net (code "7") (name "Net-(IC30-SW)") (class "Default")
      (node (ref "IC30") (pin "9") (pinfunction "SW_9") (pintype "output"))
      (node (ref "L1") (pin "1") (pinfunction "1_1") (pintype "passive"))
    )
    (net (code "8") (name "Net-(LD4-A)") (class "Default")
      (node (ref "LD4") (pin "2") (pinfunction "A_2") (pintype "passive"))
      (node (ref "R6") (pin "1") (pinfunction "1_1") (pintype "passive"))
    )
    (net (code "9") (name "Net-(LD7-A)") (class "Default")
      (node (ref "LD7") (pin "2") (pinfunction "A_2") (pintype "passive"))
      (node (ref "R8") (pin "2") (pinfunction "2_2") (pintype "passive"))
    )
    (net (code "10") (name "Net-(LD9-A)") (class "Default")
      (node (ref "LD9") (pin "2") (pinfunction "A_2") (pintype "passive"))
      (node (ref "R10") (pin "2") (pinfunction "2_2") (pintype "passive"))
    )
    (net (code "11") (name "P3V3") (class "Default")
      (node (ref "C14") (pin "2") (pinfunction "2_2") (pintype "passive"))
      (node (ref "C15") (pin "2") (pinfunction "2_2") (pintype "passive"))
      (node (ref "C16") (pin "2") (pinfunction "2_2") (pintype "passive"))
      (node (ref "C17") (pin "2") (pinfunction "2_2") (pintype "passive"))
      (node (ref "C18") (pin "1") (pinfunction "1_1") (pintype "passive"))
      (node (ref "C19") (pin "2") (pinfunction "2_2") (pintype "passive"))
      (node (ref "C20") (pin "2") (pinfunction "2_2") (pintype "passive"))
      (node (ref "C21") (pin "2") (pinfunction "2_2") (pintype "passive"))
      (node (ref "C22") (pin "2") (pinfunction "2_2") (pintype "passive"))
      (node (ref "C23") (pin "2") (pinfunction "2_2") (pintype "passive"))
      (node (ref "C24") (pin "2") (pinfunction "2_2") (pintype "passive"))
      (node (ref "C53") (pin "2") (pinfunction "2_2") (pintype "passive"))
      (node (ref "C54") (pin "2") (pinfunction "2_2") (pintype "passive"))
      (node (ref "C55") (pin "2") (pinfunction "2_2") (pintype "passive"))
      (node (ref "C56") (pin "2") (pinfunction "2_2") (pintype "passive"))
      (node (ref "C69") (pin "2") (pinfunction "2_2") (pintype "passive"))
      (node (ref "C70") (pin "2") (pinfunction "2_2") (pintype "passive"))
      (node (ref "C71") (pin "1") (pinfunction "1_1") (pintype "passive"))
      (node (ref "C72") (pin "2") (pinfunction "2_2") (pintype "passive"))
      (node (ref "C73") (pin "2") (pinfunction "2_2") (pintype "passive"))
      (node (ref "IC30") (pin "10") (pinfunction "VOS_10") (pintype "input"))
      (node (ref "IC30") (pin "8") (pinfunction "SLEEP_8") (pintype "input"))
      (node (ref "L1") (pin "2") (pinfunction "2_2") (pintype "passive"))
      (node (ref "R167") (pin "2") (pinfunction "2_2") (pintype "passive"))
      (node (ref "R8") (pin "1") (pinfunction "1_1") (pintype "passive"))
    )
    (net (code "12") (name "P3V3_MP") (class "Default")
      (node (ref "R10") (pin "1") (pinfunction "1_1") (pintype "passive"))
    )
    (net (code "13") (name "P5V0_ISO1") (class "Default")
      (node (ref "B9") (pin "1") (pinfunction "1_1") (pintype "bidirectional"))
      (node (ref "C2") (pin "2") (pinfunction "2_2") (pintype "passive"))
      (node (ref "C48") (pin "2") (pinfunction "2_2") (pintype "passive"))
      (node (ref "C49") (pin "2") (pinfunction "2_2") (pintype "passive"))
      (node (ref "C50") (pin "2") (pinfunction "2_2") (pintype "passive"))
      (node (ref "C51") (pin "2") (pinfunction "2_2") (pintype "passive"))
      (node (ref "C52") (pin "1") (pinfunction "1_1") (pintype "passive"))
      (node (ref "L2") (pin "1") (pinfunction "1_1") (pintype "passive"))
    )
    (net (code "14") (name "P5V0_ISO2") (class "Default")
      (node (ref "B11") (pin "1") (pinfunction "1_1") (pintype "bidirectional"))
      (node (ref "C28") (pin "2") (pinfunction "2_2") (pintype "passive"))
      (node (ref "C29") (pin "2") (pinfunction "2_2") (pintype "passive"))
      (node (ref "C3") (pin "2") (pinfunction "2_2") (pintype "passive"))
      (node (ref "C30") (pin "2") (pinfunction "2_2") (pintype "passive"))
      (node (ref "C31") (pin "2") (pinfunction "2_2") (pintype "passive"))
      (node (ref "C32") (pin "1") (pinfunction "1_1") (pintype "passive"))
      (node (ref "L3") (pin "1") (pinfunction "1_1") (pintype "passive"))
    )
    (net (code "15") (name "P12V0") (class "Default")
      (node (ref "C33") (pin "2") (pinfunction "2_2") (pintype "passive"))
      (node (ref "C34") (pin "1") (pinfunction "1_1") (pintype "passive"))
      (node (ref "C35") (pin "2") (pinfunction "2_2") (pintype "passive"))
      (node (ref "C36") (pin "1") (pinfunction "1_1") (pintype "passive"))
      (node (ref "C74") (pin "2") (pinfunction "2_2") (pintype "passive"))
      (node (ref "C75") (pin "2") (pinfunction "2_2") (pintype "passive"))
      (node (ref "IC1") (pin "3") (pinfunction "+Vin_3") (pintype "power_in"))
      (node (ref "IC12") (pin "1") (pinfunction "+Vin_1") (pintype "power_in"))
      (node (ref "IC2") (pin "3") (pinfunction "+Vin_3") (pintype "power_in"))
      (node (ref "IC30") (pin "2") (pinfunction "VIN_2") (pintype "input"))
      (node (ref "IC30") (pin "3") (pinfunction "EN_3") (pintype "input"))
      (node (ref "IC31") (pin "1") (pinfunction "+Vin_1") (pintype "power_in"))
      (node (ref "R6") (pin "2") (pinfunction "2_2") (pintype "passive"))
    )
    (net (code "16") (name "unconnected-(IC1-na-Pad14)") (class "Default")
      (node (ref "IC1") (pin "14") (pinfunction "na_14") (pintype "passive"))
    )
    (net (code "17") (name "unconnected-(IC2-na-Pad14)") (class "Default")
      (node (ref "IC2") (pin "14") (pinfunction "na_14") (pintype "passive"))
    )
    (net (code "18") (name "unconnected-(IC30-NC-Pad4)") (class "Default")
      (node (ref "IC30") (pin "4") (pinfunction "NC_4") (pintype "passive"))
    )
    (net (code "19") (name "unconnected-(IC30-PG-Pad7)") (class "Default")
      (node (ref "IC30") (pin "7") (pinfunction "PG_7") (pintype "output"))
    )
  )
)
